# Busmaster.net
KiCad netlist of a schematic drawn in Altium Designer
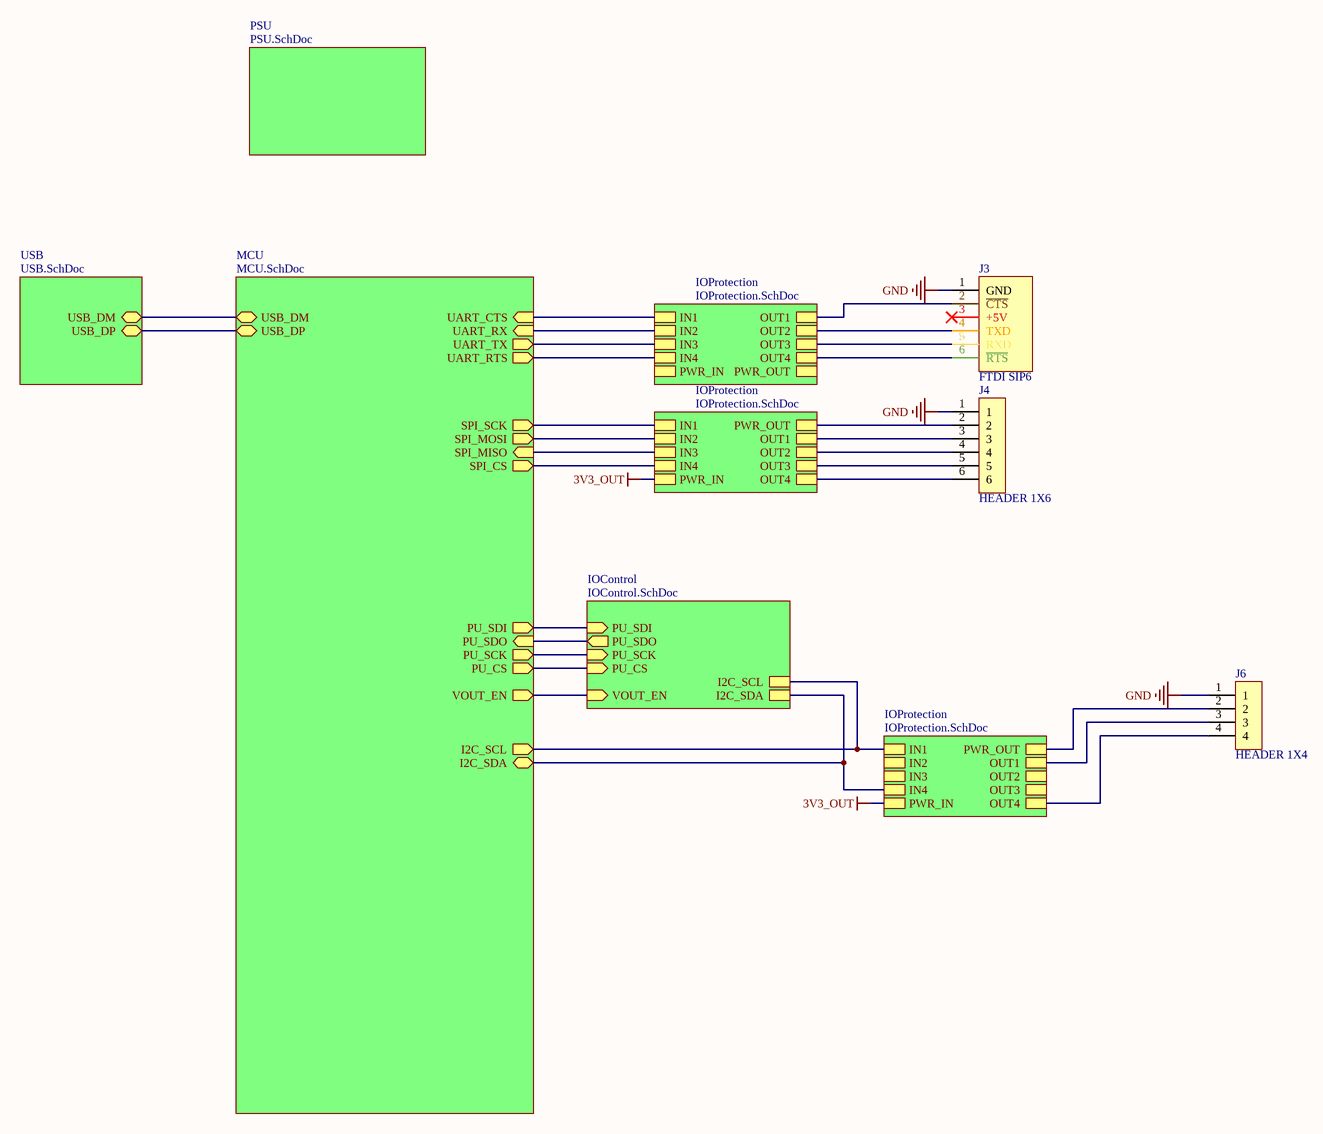
[diagram p0: Busmaster.SchDoc]

(export (version "E")
  (design (tool "Eeschema 10.0.6"))
  (components
    (comp (ref "J3")
      (value "FTDI SIP6")
      (footprint "HIROSE_A2-6PA-2.54DSA")
      (description "FTDI Serial Header")
      (fields
        (field (name "MANUFACTURER") "Hirose Electric Co Ltd")
        (field (name "MANUFACTURER PART NUMBER") "A2-6PA-2.54DSA(71)")
      )
      (libsource (lib "library") (part "FTDI_TTL_232R"))
    )
    (comp (ref "J4")
      (value "HEADER 1X6")
      (footprint "HIROSE_A2-6PA-2.54DSA")
      (description "CONN 6-pin 2.54mm pitch TH single row")
      (fields
        (field (name "MANUFACTURER") "Hirose")
        (field (name "MANUFACTURER PART NUMBER") "A2-6PA-2.54DSA")
      )
      (libsource (lib "library") (part "HIROSE_A2-6PA-2.54DSA"))
    )
    (comp (ref "J6")
      (value "HEADER 1X4")
      (footprint "HIROSE_A2-4PA-2.54DSA")
      (description "CONN 4-pin 2.54mm pitch TH single row")
      (fields
        (field (name "MANUFACTURER") "Hirose")
        (field (name "MANUFACTURER PART NUMBER") "A2-4PA-2.54DSA")
      )
      (libsource (lib "library") (part "HIROSE_A2-4PA-2.54DSA"))
    )
  )
  (nets
    (net (code "8") (name "/OUT1") (class "Default")
      (node (ref "J3") (pin "2") (pinfunction "~{CTS}_2") (pintype "passive"))
    )
    (net (code "9") (name "/OUT1_1") (class "Default")
      (node (ref "J4") (pin "3") (pinfunction "3_3") (pintype "passive"))
    )
    (net (code "10") (name "/OUT1_2") (class "Default")
      (node (ref "J6") (pin "3") (pinfunction "3_3") (pintype "passive"))
    )
    (net (code "11") (name "/OUT2") (class "Default")
      (node (ref "J3") (pin "4") (pinfunction "TXD_4") (pintype "passive"))
    )
    (net (code "12") (name "/OUT2_1") (class "Default")
      (node (ref "J4") (pin "4") (pinfunction "4_4") (pintype "passive"))
    )
    (net (code "14") (name "/OUT3") (class "Default")
      (node (ref "J3") (pin "5") (pinfunction "RXD_5") (pintype "passive"))
    )
    (net (code "15") (name "/OUT3_1") (class "Default")
      (node (ref "J4") (pin "5") (pinfunction "5_5") (pintype "passive"))
    )
    (net (code "17") (name "/OUT4") (class "Default")
      (node (ref "J3") (pin "6") (pinfunction "~{RTS}_6") (pintype "passive"))
    )
    (net (code "18") (name "/OUT4_1") (class "Default")
      (node (ref "J4") (pin "6") (pinfunction "6_6") (pintype "passive"))
    )
    (net (code "19") (name "/OUT4_2") (class "Default")
      (node (ref "J6") (pin "4") (pinfunction "4_4") (pintype "passive"))
    )
    (net (code "26") (name "/PWR_OUT_1") (class "Default")
      (node (ref "J4") (pin "2") (pinfunction "2_2") (pintype "passive"))
    )
    (net (code "27") (name "/PWR_OUT_2") (class "Default")
      (node (ref "J6") (pin "2") (pinfunction "2_2") (pintype "passive"))
    )
    (net (code "37") (name "GND") (class "Default")
      (node (ref "J3") (pin "1") (pinfunction "GND_1") (pintype "passive"))
      (node (ref "J4") (pin "1") (pinfunction "1_1") (pintype "passive"))
      (node (ref "J6") (pin "1") (pinfunction "1_1") (pintype "passive"))
    )
    (net (code "38") (name "unconnected-(J3-+5V-Pad3)") (class "Default")
      (node (ref "J3") (pin "3") (pinfunction "+5V_3") (pintype "passive+no_connect"))
    )
  )
)
